# senderNode_Uno.net
KiCad netlist of a schematic drawn in EAGLE
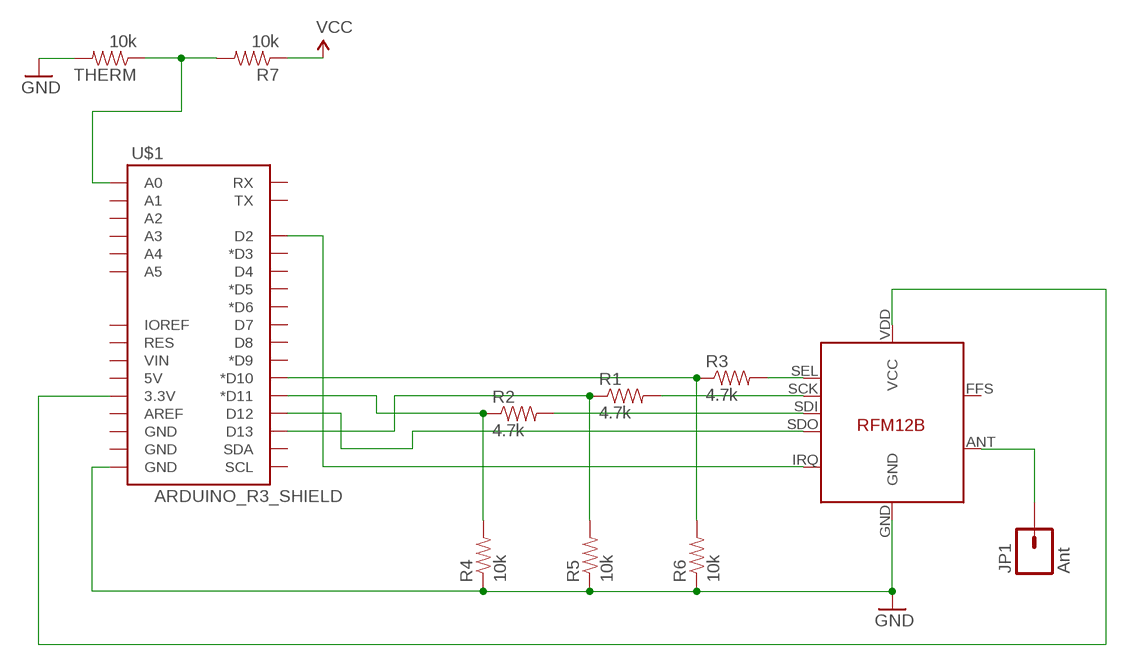
[diagram p0: schematic, sheet 1]

(export (version "E")
  (design (tool "Eeschema 10.0.6"))
  (components
    (comp (ref "JP1")
      (value "Ant")
      (footprint "eagle-import:1X01_LONGPAD")
      (libsource (lib "eagle-import") (part "M01PTH_LONGPAD"))
    )
    (comp (ref "R1")
      (value "4.7k")
      (footprint "eagle-import:AXIAL-0.3")
      (libsource (lib "eagle-import") (part "RESISTORAXIAL-0.3"))
    )
    (comp (ref "R2")
      (value "4.7k")
      (footprint "eagle-import:AXIAL-0.3")
      (libsource (lib "eagle-import") (part "RESISTORAXIAL-0.3"))
    )
    (comp (ref "R3")
      (value "4.7k")
      (footprint "eagle-import:AXIAL-0.3")
      (libsource (lib "eagle-import") (part "RESISTORAXIAL-0.3"))
    )
    (comp (ref "R4")
      (value "10k")
      (footprint "eagle-import:AXIAL-0.3")
      (libsource (lib "eagle-import") (part "RESISTORAXIAL-0.3"))
    )
    (comp (ref "R5")
      (value "10k")
      (footprint "eagle-import:AXIAL-0.3")
      (libsource (lib "eagle-import") (part "RESISTORAXIAL-0.3"))
    )
    (comp (ref "R6")
      (value "10k")
      (footprint "eagle-import:AXIAL-0.3")
      (libsource (lib "eagle-import") (part "RESISTORAXIAL-0.3"))
    )
    (comp (ref "R7")
      (value "10k")
      (footprint "eagle-import:AXIAL-0.3")
      (libsource (lib "eagle-import") (part "RESISTORAXIAL-0.3"))
    )
    (comp (ref "THERM")
      (value "10k")
      (footprint "eagle-import:AXIAL-0.3")
      (libsource (lib "eagle-import") (part "RESISTORAXIAL-0.3"))
    )
    (comp (ref "U$1")
      (value "ARDUINO_R3_SHIELD")
      (footprint "eagle-import:UNO_R3_SHIELD")
      (libsource (lib "eagle-import") (part "ARDUINO_R3_SHIELD"))
    )
    (comp (ref "U$2")
      (value "RFM12B")
      (footprint "eagle-import:RFM12B")
      (libsource (lib "eagle-import") (part "RFM12B"))
    )
  )
  (nets
    (net (code "1") (name "GND") (class "Default")
      (node (ref "R4") (pin "P$1") (pinfunction "1_P$1") (pintype "passive"))
      (node (ref "R5") (pin "P$1") (pinfunction "1_P$1") (pintype "passive"))
      (node (ref "R6") (pin "P$1") (pinfunction "1_P$1") (pintype "passive"))
      (node (ref "THERM") (pin "P$2") (pinfunction "2_P$2") (pintype "passive"))
      (node (ref "U$1") (pin "GND@0") (pinfunction "GND_GND@0") (pintype "bidirectional"))
      (node (ref "U$2") (pin "GND") (pinfunction "GND_GND") (pintype "power_in"))
    )
    (net (code "2") (name "Net-(JP1-Pad1)") (class "Default")
      (node (ref "JP1") (pin "1") (pinfunction "1_1") (pintype "passive"))
      (node (ref "U$2") (pin "ANT") (pinfunction "ANT_ANT") (pintype "passive"))
    )
    (net (code "3") (name "Net-(R1-1)") (class "Default")
      (node (ref "R1") (pin "P$1") (pinfunction "1_P$1") (pintype "passive"))
      (node (ref "R5") (pin "P$2") (pinfunction "2_P$2") (pintype "passive"))
      (node (ref "U$1") (pin "D13") (pinfunction "D13_D13") (pintype "bidirectional"))
    )
    (net (code "4") (name "Net-(R1-2)") (class "Default")
      (node (ref "R1") (pin "P$2") (pinfunction "2_P$2") (pintype "passive"))
      (node (ref "U$2") (pin "SCK") (pinfunction "SCK_SCK") (pintype "input"))
    )
    (net (code "5") (name "Net-(R2-1)") (class "Default")
      (node (ref "R2") (pin "P$1") (pinfunction "1_P$1") (pintype "passive"))
      (node (ref "R4") (pin "P$2") (pinfunction "2_P$2") (pintype "passive"))
      (node (ref "U$1") (pin "D11") (pinfunction "*D11_D11") (pintype "bidirectional"))
    )
    (net (code "6") (name "Net-(R2-2)") (class "Default")
      (node (ref "R2") (pin "P$2") (pinfunction "2_P$2") (pintype "passive"))
      (node (ref "U$2") (pin "SDI") (pinfunction "SDI_SDI") (pintype "input"))
    )
    (net (code "7") (name "Net-(R3-1)") (class "Default")
      (node (ref "R3") (pin "P$1") (pinfunction "1_P$1") (pintype "passive"))
      (node (ref "R6") (pin "P$2") (pinfunction "2_P$2") (pintype "passive"))
      (node (ref "U$1") (pin "D10") (pinfunction "*D10_D10") (pintype "bidirectional"))
    )
    (net (code "8") (name "Net-(R3-2)") (class "Default")
      (node (ref "R3") (pin "P$2") (pinfunction "2_P$2") (pintype "passive"))
      (node (ref "U$2") (pin "SEL") (pinfunction "SEL_SEL") (pintype "input"))
    )
    (net (code "9") (name "Net-(R7-2)") (class "Default")
      (node (ref "R7") (pin "P$2") (pinfunction "2_P$2") (pintype "passive"))
      (node (ref "THERM") (pin "P$1") (pinfunction "1_P$1") (pintype "passive"))
      (node (ref "U$1") (pin "A0") (pinfunction "A0_A0") (pintype "bidirectional"))
    )
    (net (code "10") (name "Net-(U$1-PadD2)") (class "Default")
      (node (ref "U$1") (pin "D2") (pinfunction "D2_D2") (pintype "bidirectional"))
      (node (ref "U$2") (pin "IRQ") (pinfunction "IRQ_IRQ") (pintype "open_collector"))
    )
    (net (code "11") (name "Net-(U$1-PadD12)") (class "Default")
      (node (ref "U$1") (pin "D12") (pinfunction "D12_D12") (pintype "bidirectional"))
      (node (ref "U$2") (pin "SDO") (pinfunction "SDO_SDO") (pintype "output"))
    )
    (net (code "12") (name "Net-(U$2-VCC)") (class "Default")
      (node (ref "U$1") (pin "3.3V") (pinfunction "3.3V_3.3V") (pintype "bidirectional"))
      (node (ref "U$2") (pin "VDD") (pinfunction "VCC_VDD") (pintype "power_in"))
    )
    (net (code "13") (name "VCC") (class "Default")
      (node (ref "R7") (pin "P$1") (pinfunction "1_P$1") (pintype "passive"))
    )
    (net (code "14") (name "unconnected-(U$1-*D3-PadD3)") (class "Default")
      (node (ref "U$1") (pin "D3") (pinfunction "*D3_D3") (pintype "bidirectional"))
    )
    (net (code "15") (name "unconnected-(U$1-*D5-PadD5)") (class "Default")
      (node (ref "U$1") (pin "D5") (pinfunction "*D5_D5") (pintype "bidirectional"))
    )
    (net (code "16") (name "unconnected-(U$1-*D6-PadD6)") (class "Default")
      (node (ref "U$1") (pin "D6") (pinfunction "*D6_D6") (pintype "bidirectional"))
    )
    (net (code "17") (name "unconnected-(U$1-*D9-PadD9)") (class "Default")
      (node (ref "U$1") (pin "D9") (pinfunction "*D9_D9") (pintype "bidirectional"))
    )
    (net (code "18") (name "unconnected-(U$1-GND-PadGND@1)") (class "Default")
      (node (ref "U$1") (pin "GND@1") (pinfunction "GND_GND@1") (pintype "bidirectional"))
    )
    (net (code "19") (name "unconnected-(U$1-GND-PadGND@2)") (class "Default")
      (node (ref "U$1") (pin "GND@2") (pinfunction "GND_GND@2") (pintype "bidirectional"))
    )
    (net (code "20") (name "unconnected-(U$1-Pad5V)") (class "Default")
      (node (ref "U$1") (pin "5V") (pinfunction "5V_5V") (pintype "bidirectional"))
    )
    (net (code "21") (name "unconnected-(U$1-PadA1)") (class "Default")
      (node (ref "U$1") (pin "A1") (pinfunction "A1_A1") (pintype "bidirectional"))
    )
    (net (code "22") (name "unconnected-(U$1-PadA2)") (class "Default")
      (node (ref "U$1") (pin "A2") (pinfunction "A2_A2") (pintype "bidirectional"))
    )
    (net (code "23") (name "unconnected-(U$1-PadA3)") (class "Default")
      (node (ref "U$1") (pin "A3") (pinfunction "A3_A3") (pintype "bidirectional"))
    )
    (net (code "24") (name "unconnected-(U$1-PadA4)") (class "Default")
      (node (ref "U$1") (pin "A4") (pinfunction "A4_A4") (pintype "bidirectional"))
    )
    (net (code "25") (name "unconnected-(U$1-PadA5)") (class "Default")
      (node (ref "U$1") (pin "A5") (pinfunction "A5_A5") (pintype "bidirectional"))
    )
    (net (code "26") (name "unconnected-(U$1-PadAREF)") (class "Default")
      (node (ref "U$1") (pin "AREF") (pinfunction "AREF_AREF") (pintype "bidirectional"))
    )
    (net (code "27") (name "unconnected-(U$1-PadD4)") (class "Default")
      (node (ref "U$1") (pin "D4") (pinfunction "D4_D4") (pintype "bidirectional"))
    )
    (net (code "28") (name "unconnected-(U$1-PadD7)") (class "Default")
      (node (ref "U$1") (pin "D7") (pinfunction "D7_D7") (pintype "bidirectional"))
    )
    (net (code "29") (name "unconnected-(U$1-PadD8)") (class "Default")
      (node (ref "U$1") (pin "D8") (pinfunction "D8_D8") (pintype "bidirectional"))
    )
    (net (code "30") (name "unconnected-(U$1-PadIOREF)") (class "Default")
      (node (ref "U$1") (pin "IOREF") (pinfunction "IOREF_IOREF") (pintype "bidirectional"))
    )
    (net (code "31") (name "unconnected-(U$1-PadRES)") (class "Default")
      (node (ref "U$1") (pin "RES") (pinfunction "RES_RES") (pintype "bidirectional"))
    )
    (net (code "32") (name "unconnected-(U$1-PadRX)") (class "Default")
      (node (ref "U$1") (pin "RX") (pinfunction "RX_RX") (pintype "bidirectional"))
    )
    (net (code "33") (name "unconnected-(U$1-PadSCL)") (class "Default")
      (node (ref "U$1") (pin "SCL") (pinfunction "SCL_SCL") (pintype "bidirectional"))
    )
    (net (code "34") (name "unconnected-(U$1-PadSDA)") (class "Default")
      (node (ref "U$1") (pin "SDA") (pinfunction "SDA_SDA") (pintype "bidirectional"))
    )
    (net (code "35") (name "unconnected-(U$1-PadTX)") (class "Default")
      (node (ref "U$1") (pin "TX") (pinfunction "TX_TX") (pintype "bidirectional"))
    )
    (net (code "36") (name "unconnected-(U$1-PadVIN)") (class "Default")
      (node (ref "U$1") (pin "VIN") (pinfunction "VIN_VIN") (pintype "bidirectional"))
    )
    (net (code "37") (name "unconnected-(U$2-PadFFS)") (class "Default")
      (node (ref "U$2") (pin "FFS") (pinfunction "FFS_FFS") (pintype "bidirectional"))
    )
  )
)
